# digidisk.net
KiCad netlist of a schematic drawn in Altium Designer
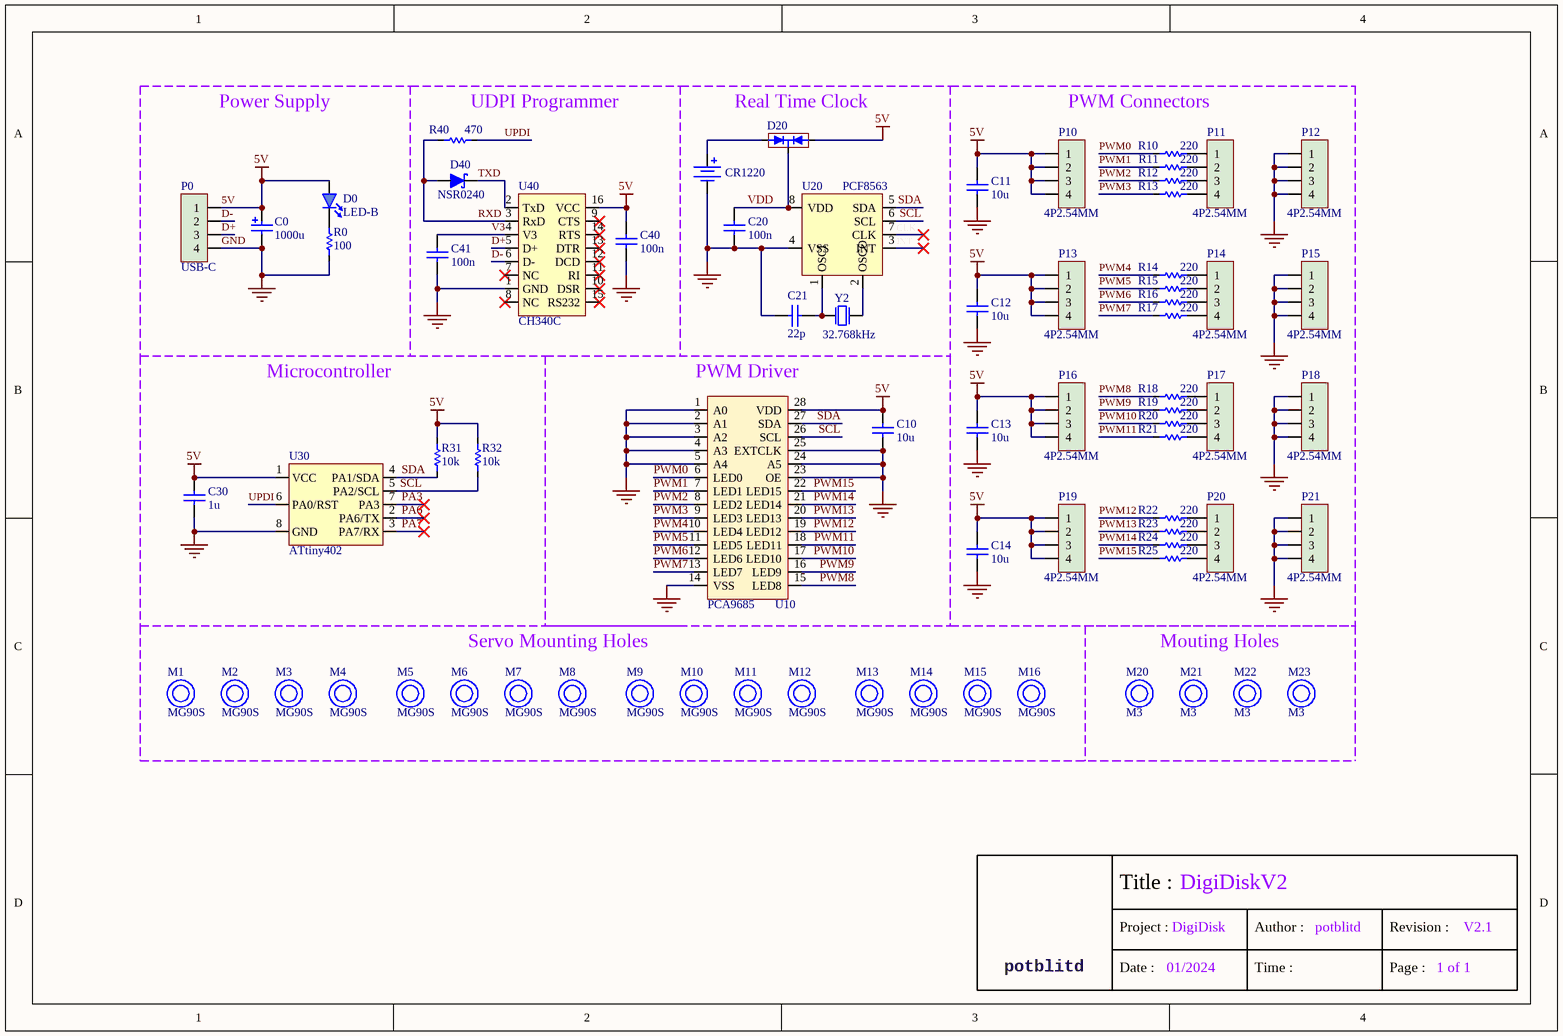
[diagram p0: digidisk.SchDoc]

(export (version "E")
  (design (tool "Eeschema 10.0.6"))
  (components
    (comp (ref "BT20")
      (value "CR1220")
      (footprint "CR1220-H")
      (description "Coin cell battery 3V")
      (libsource (lib "AltiumLib") (part "Battery 3V"))
    )
    (comp (ref "C0")
      (value "1000u")
      (footprint "10X10.2")
      (description "Electrolytic Capacitor")
      (libsource (lib "AltiumLib") (part "PCapacitor"))
    )
    (comp (ref "C10")
      (value "10u")
      (footprint "0603CM")
      (description "Capacitor 10u")
      (fields (field (name "Comment") "Capacitor"))
      (libsource (lib "Simulation Generic Components") (part "Capacitor"))
    )
    (comp (ref "C11")
      (value "10u")
      (footprint "0603CM")
      (description "Capacitor 10u")
      (fields (field (name "Comment") "Capacitor"))
      (libsource (lib "Simulation Generic Components") (part "Capacitor"))
    )
    (comp (ref "C12")
      (value "10u")
      (footprint "0603CM")
      (description "Capacitor 10u")
      (fields (field (name "Comment") "Capacitor"))
      (libsource (lib "Simulation Generic Components") (part "Capacitor"))
    )
    (comp (ref "C13")
      (value "10u")
      (footprint "0603CM")
      (description "Capacitor 10u")
      (fields (field (name "Comment") "Capacitor"))
      (libsource (lib "Simulation Generic Components") (part "Capacitor"))
    )
    (comp (ref "C14")
      (value "10u")
      (footprint "0603CM")
      (description "Capacitor 10u")
      (fields (field (name "Comment") "Capacitor"))
      (libsource (lib "Simulation Generic Components") (part "Capacitor"))
    )
    (comp (ref "C20")
      (value "100n")
      (footprint "0603CM")
      (description "Capacitor 100nF ±10% 50V")
      (fields (field (name "Comment") "Capacitor"))
      (libsource (lib "Simulation Generic Components") (part "Capacitor"))
    )
    (comp (ref "C21")
      (value "22p")
      (footprint "0603CM")
      (description "Capacitor 22pF ±5% 50V")
      (fields (field (name "Comment") "Capacitor"))
      (libsource (lib "Simulation Generic Components") (part "Capacitor"))
    )
    (comp (ref "C30")
      (value "Capacitor")
      (footprint "0603CM")
      (description "Capacitor 1uF")
      (fields (field (name "ALTIUM_VALUE") "1u"))
      (libsource (lib "Simulation Generic Components") (part "Capacitor"))
    )
    (comp (ref "C40")
      (value "100n")
      (footprint "0603CM")
      (description "Capacitor 100nF ±10% 50V")
      (fields (field (name "Comment") "Capacitor"))
      (libsource (lib "Simulation Generic Components") (part "Capacitor"))
    )
    (comp (ref "C41")
      (value "100n")
      (footprint "0603CM")
      (description "Capacitor 100nF ±10% 50V")
      (fields (field (name "Comment") "Capacitor"))
      (libsource (lib "Simulation Generic Components") (part "Capacitor"))
    )
    (comp (ref "D0")
      (value "LED-B")
      (footprint "0603DM")
      (description "General LED symbol")
      (libsource (lib "AltiumLib") (part "LED-B"))
    )
    (comp (ref "D20")
      (value "BAS40-05")
      (footprint "SOT23-3 M")
      (description "General symbol for a dual diode")
      (libsource (lib "AltiumLib") (part "Dual Diode 2"))
    )
    (comp (ref "D40")
      (value "NSR0240")
      (footprint "SOD-323 M")
      (description "Schottky Barrier Rectifiers")
      (libsource (lib "AltiumLib") (part "Schottky Diode"))
    )
    (comp (ref "M1")
      (value "MG90S")
      (footprint "HOLE-SG90-2")
      (description "Genreal symbol for mechanical mounting hole")
      (libsource (lib "AltiumLib") (part "Mounting Hole noGD"))
    )
    (comp (ref "M2")
      (value "MG90S")
      (footprint "HOLE-SG90-2")
      (description "Genreal symbol for mechanical mounting hole")
      (libsource (lib "AltiumLib") (part "Mounting Hole noGD"))
    )
    (comp (ref "M3")
      (value "MG90S")
      (footprint "HOLE-SG90-2")
      (description "Genreal symbol for mechanical mounting hole")
      (libsource (lib "AltiumLib") (part "Mounting Hole noGD"))
    )
    (comp (ref "M4")
      (value "MG90S")
      (footprint "HOLE-SG90-2")
      (description "Genreal symbol for mechanical mounting hole")
      (libsource (lib "AltiumLib") (part "Mounting Hole noGD"))
    )
    (comp (ref "M5")
      (value "MG90S")
      (footprint "HOLE-SG90-2")
      (description "Genreal symbol for mechanical mounting hole")
      (libsource (lib "AltiumLib") (part "Mounting Hole noGD"))
    )
    (comp (ref "M6")
      (value "MG90S")
      (footprint "HOLE-SG90-2")
      (description "Genreal symbol for mechanical mounting hole")
      (libsource (lib "AltiumLib") (part "Mounting Hole noGD"))
    )
    (comp (ref "M7")
      (value "MG90S")
      (footprint "HOLE-SG90-2")
      (description "Genreal symbol for mechanical mounting hole")
      (libsource (lib "AltiumLib") (part "Mounting Hole noGD"))
    )
    (comp (ref "M8")
      (value "MG90S")
      (footprint "HOLE-SG90-2")
      (description "Genreal symbol for mechanical mounting hole")
      (libsource (lib "AltiumLib") (part "Mounting Hole noGD"))
    )
    (comp (ref "M9")
      (value "MG90S")
      (footprint "HOLE-SG90-2")
      (description "Genreal symbol for mechanical mounting hole")
      (libsource (lib "AltiumLib") (part "Mounting Hole noGD"))
    )
    (comp (ref "M10")
      (value "MG90S")
      (footprint "HOLE-SG90-2")
      (description "Genreal symbol for mechanical mounting hole")
      (libsource (lib "AltiumLib") (part "Mounting Hole noGD"))
    )
    (comp (ref "M11")
      (value "MG90S")
      (footprint "HOLE-SG90-2")
      (description "Genreal symbol for mechanical mounting hole")
      (libsource (lib "AltiumLib") (part "Mounting Hole noGD"))
    )
    (comp (ref "M12")
      (value "MG90S")
      (footprint "HOLE-SG90-2")
      (description "Genreal symbol for mechanical mounting hole")
      (libsource (lib "AltiumLib") (part "Mounting Hole noGD"))
    )
    (comp (ref "M13")
      (value "MG90S")
      (footprint "HOLE-SG90-2")
      (description "Genreal symbol for mechanical mounting hole")
      (libsource (lib "AltiumLib") (part "Mounting Hole noGD"))
    )
    (comp (ref "M14")
      (value "MG90S")
      (footprint "HOLE-SG90-2")
      (description "Genreal symbol for mechanical mounting hole")
      (libsource (lib "AltiumLib") (part "Mounting Hole noGD"))
    )
    (comp (ref "M15")
      (value "MG90S")
      (footprint "HOLE-SG90-2")
      (description "Genreal symbol for mechanical mounting hole")
      (libsource (lib "AltiumLib") (part "Mounting Hole noGD"))
    )
    (comp (ref "M16")
      (value "MG90S")
      (footprint "HOLE-SG90-2")
      (description "Genreal symbol for mechanical mounting hole")
      (libsource (lib "AltiumLib") (part "Mounting Hole noGD"))
    )
    (comp (ref "M20")
      (value "M3")
      (footprint "HOLE-M3-simple")
      (description "Genreal symbol for mechanical mounting hole")
      (libsource (lib "AltiumLib") (part "Mounting Hole noGD"))
    )
    (comp (ref "M21")
      (value "M3")
      (footprint "HOLE-M3-simple")
      (description "Genreal symbol for mechanical mounting hole")
      (libsource (lib "AltiumLib") (part "Mounting Hole noGD"))
    )
    (comp (ref "M22")
      (value "M3")
      (footprint "HOLE-M3-simple")
      (description "Genreal symbol for mechanical mounting hole")
      (libsource (lib "AltiumLib") (part "Mounting Hole noGD"))
    )
    (comp (ref "M23")
      (value "M3")
      (footprint "HOLE-M3-simple")
      (description "Genreal symbol for mechanical mounting hole")
      (libsource (lib "AltiumLib") (part "Mounting Hole noGD"))
    )
    (comp (ref "P0")
      (value "USB-C")
      (footprint "USB-C module 2.8mm")
      (description "General 4-pin connection")
      (libsource (lib "") (part "4-pins Header_1"))
    )
    (comp (ref "P10")
      (value "4P2.54MM")
      (footprint "4P-2.54mm")
      (description "General 4-pin connection")
      (libsource (lib "AltiumLib") (part "4-pins Header"))
    )
    (comp (ref "P11")
      (value "4P2.54MM")
      (footprint "4P-2.54mm")
      (description "General 4-pin connection")
      (libsource (lib "AltiumLib") (part "4-pins Header"))
    )
    (comp (ref "P12")
      (value "4P2.54MM")
      (footprint "4P-2.54mm")
      (description "General 4-pin connection")
      (libsource (lib "AltiumLib") (part "4-pins Header"))
    )
    (comp (ref "P13")
      (value "4P2.54MM")
      (footprint "4P-2.54mm")
      (description "General 4-pin connection")
      (libsource (lib "AltiumLib") (part "4-pins Header"))
    )
    (comp (ref "P14")
      (value "4P2.54MM")
      (footprint "4P-2.54mm")
      (description "General 4-pin connection")
      (libsource (lib "AltiumLib") (part "4-pins Header"))
    )
    (comp (ref "P15")
      (value "4P2.54MM")
      (footprint "4P-2.54mm")
      (description "General 4-pin connection")
      (libsource (lib "AltiumLib") (part "4-pins Header"))
    )
    (comp (ref "P16")
      (value "4P2.54MM")
      (footprint "4P-2.54mm")
      (description "General 4-pin connection")
      (libsource (lib "AltiumLib") (part "4-pins Header"))
    )
    (comp (ref "P17")
      (value "4P2.54MM")
      (footprint "4P-2.54mm")
      (description "General 4-pin connection")
      (libsource (lib "AltiumLib") (part "4-pins Header"))
    )
    (comp (ref "P18")
      (value "4P2.54MM")
      (footprint "4P-2.54mm")
      (description "General 4-pin connection")
      (libsource (lib "AltiumLib") (part "4-pins Header"))
    )
    (comp (ref "P19")
      (value "4P2.54MM")
      (footprint "4P-2.54mm")
      (description "General 4-pin connection")
      (libsource (lib "AltiumLib") (part "4-pins Header"))
    )
    (comp (ref "P20")
      (value "4P2.54MM")
      (footprint "4P-2.54mm")
      (description "General 4-pin connection")
      (libsource (lib "AltiumLib") (part "4-pins Header"))
    )
    (comp (ref "P21")
      (value "4P2.54MM")
      (footprint "4P-2.54mm")
      (description "General 4-pin connection")
      (libsource (lib "AltiumLib") (part "4-pins Header"))
    )
    (comp (ref "R0")
      (value "100")
      (footprint "0603RM")
      (description "Resistor")
      (libsource (lib "AltiumLib") (part "RES"))
    )
    (comp (ref "R10")
      (value "220")
      (footprint "0603RM")
      (description "Resistor")
      (libsource (lib "AltiumLib") (part "RES"))
    )
    (comp (ref "R11")
      (value "220")
      (footprint "0603RM")
      (description "Resistor")
      (libsource (lib "AltiumLib") (part "RES"))
    )
    (comp (ref "R12")
      (value "220")
      (footprint "0603RM")
      (description "Resistor")
      (libsource (lib "AltiumLib") (part "RES"))
    )
    (comp (ref "R13")
      (value "220")
      (footprint "0603RM")
      (description "Resistor")
      (libsource (lib "AltiumLib") (part "RES"))
    )
    (comp (ref "R14")
      (value "220")
      (footprint "0603RM")
      (description "Resistor")
      (libsource (lib "AltiumLib") (part "RES"))
    )
    (comp (ref "R15")
      (value "220")
      (footprint "0603RM")
      (description "Resistor")
      (libsource (lib "AltiumLib") (part "RES"))
    )
    (comp (ref "R16")
      (value "220")
      (footprint "0603RM")
      (description "Resistor")
      (libsource (lib "AltiumLib") (part "RES"))
    )
    (comp (ref "R17")
      (value "220")
      (footprint "0603RM")
      (description "Resistor")
      (libsource (lib "AltiumLib") (part "RES"))
    )
    (comp (ref "R18")
      (value "220")
      (footprint "0603RM")
      (description "Resistor")
      (libsource (lib "AltiumLib") (part "RES"))
    )
    (comp (ref "R19")
      (value "220")
      (footprint "0603RM")
      (description "Resistor")
      (libsource (lib "AltiumLib") (part "RES"))
    )
    (comp (ref "R20")
      (value "220")
      (footprint "0603RM")
      (description "Resistor")
      (libsource (lib "AltiumLib") (part "RES"))
    )
    (comp (ref "R21")
      (value "220")
      (footprint "0603RM")
      (description "Resistor")
      (libsource (lib "AltiumLib") (part "RES"))
    )
    (comp (ref "R22")
      (value "220")
      (footprint "0603RM")
      (description "Resistor")
      (libsource (lib "AltiumLib") (part "RES"))
    )
    (comp (ref "R23")
      (value "220")
      (footprint "0603RM")
      (description "Resistor")
      (libsource (lib "AltiumLib") (part "RES"))
    )
    (comp (ref "R24")
      (value "220")
      (footprint "0603RM")
      (description "Resistor")
      (libsource (lib "AltiumLib") (part "RES"))
    )
    (comp (ref "R25")
      (value "220")
      (footprint "0603RM")
      (description "Resistor")
      (libsource (lib "AltiumLib") (part "RES"))
    )
    (comp (ref "R31")
      (value "10k")
      (footprint "0603RM")
      (description "Resistor")
      (libsource (lib "AltiumLib") (part "RES"))
    )
    (comp (ref "R32")
      (value "10k")
      (footprint "0603RM")
      (description "Resistor")
      (libsource (lib "AltiumLib") (part "RES"))
    )
    (comp (ref "R40")
      (value "470")
      (footprint "0603RM")
      (description "Resistor")
      (libsource (lib "AltiumLib") (part "RES"))
    )
    (comp (ref "U10")
      (value "PCA9685")
      (footprint "TSSOP-28 M")
      (description "16-channel, 12-bit PWM Fm+ I2C-bus LED controller")
      (libsource (lib "AltiumLib") (part "PCA9685"))
    )
    (comp (ref "U20")
      (value "PCF8563")
      (footprint "SOP-8 M")
      (description "IC real-time clock with alarm interrupt")
      (libsource (lib "AltiumLib") (part "RTC-8563"))
    )
    (comp (ref "U30")
      (value "ATtiny402")
      (footprint "SOP-8 M")
      (description "tiny AVR 8-pin microcontroller")
      (fields (field (name "COMPONENT") "ATtiny402"))
      (libsource (lib "AltiumLib") (part "ATtiny202/402"))
    )
    (comp (ref "U40")
      (value "CH340C")
      (footprint "SOP-16 M")
      (description "USB to serial")
      (libsource (lib "AltiumLib") (part "CH340C-A"))
    )
    (comp (ref "Y2")
      (value "32.768kHz")
      (footprint "FC135 M")
      (description "Crystal oscillator 32.768kHz 20ppm 12.5pF")
      (fields (field (name "Comment") "Oscillator"))
      (libsource (lib "AltiumLib") (part "XO-2"))
    )
  )
  (nets
    (net (code "1") (name "/CLK") (class "Default")
      (node (ref "U20") (pin "7") (pinfunction "CLK_7") (pintype "passive+no_connect"))
    )
    (net (code "2") (name "/D+") (class "Default")
      (node (ref "P0") (pin "3") (pinfunction "3_3") (pintype "passive"))
      (node (ref "U40") (pin "5") (pinfunction "D+_5") (pintype "passive"))
    )
    (net (code "3") (name "/D-") (class "Default")
      (node (ref "P0") (pin "2") (pinfunction "2_2") (pintype "passive"))
      (node (ref "U40") (pin "6") (pinfunction "D-_6") (pintype "passive"))
    )
    (net (code "4") (name "/INT") (class "Default")
      (node (ref "U20") (pin "3") (pinfunction "INT_3") (pintype "passive+no_connect"))
    )
    (net (code "5") (name "/PA3") (class "Default")
      (node (ref "U30") (pin "7") (pinfunction "PA3_7") (pintype "passive+no_connect"))
    )
    (net (code "6") (name "/PA6") (class "Default")
      (node (ref "U30") (pin "2") (pinfunction "PA6/TX_2") (pintype "passive+no_connect"))
    )
    (net (code "7") (name "/PA7") (class "Default")
      (node (ref "U30") (pin "3") (pinfunction "PA7/RX_3") (pintype "passive+no_connect"))
    )
    (net (code "8") (name "/PWM0") (class "Default")
      (node (ref "R10") (pin "2") (pinfunction "2_2") (pintype "passive"))
      (node (ref "U10") (pin "6") (pinfunction "LED0_6") (pintype "passive"))
    )
    (net (code "9") (name "/PWM1") (class "Default")
      (node (ref "R11") (pin "2") (pinfunction "2_2") (pintype "passive"))
      (node (ref "U10") (pin "7") (pinfunction "LED1_7") (pintype "passive"))
    )
    (net (code "10") (name "/PWM2") (class "Default")
      (node (ref "R12") (pin "2") (pinfunction "2_2") (pintype "passive"))
      (node (ref "U10") (pin "8") (pinfunction "LED2_8") (pintype "passive"))
    )
    (net (code "11") (name "/PWM3") (class "Default")
      (node (ref "R13") (pin "2") (pinfunction "2_2") (pintype "passive"))
      (node (ref "U10") (pin "9") (pinfunction "LED3_9") (pintype "passive"))
    )
    (net (code "12") (name "/PWM4") (class "Default")
      (node (ref "R14") (pin "2") (pinfunction "2_2") (pintype "passive"))
      (node (ref "U10") (pin "10") (pinfunction "LED4_10") (pintype "passive"))
    )
    (net (code "13") (name "/PWM5") (class "Default")
      (node (ref "R15") (pin "2") (pinfunction "2_2") (pintype "passive"))
      (node (ref "U10") (pin "11") (pinfunction "LED5_11") (pintype "passive"))
    )
    (net (code "14") (name "/PWM6") (class "Default")
      (node (ref "R16") (pin "2") (pinfunction "2_2") (pintype "passive"))
      (node (ref "U10") (pin "12") (pinfunction "LED6_12") (pintype "passive"))
    )
    (net (code "15") (name "/PWM7") (class "Default")
      (node (ref "R17") (pin "2") (pinfunction "2_2") (pintype "passive"))
      (node (ref "U10") (pin "13") (pinfunction "LED7_13") (pintype "passive"))
    )
    (net (code "16") (name "/PWM8") (class "Default")
      (node (ref "R18") (pin "2") (pinfunction "2_2") (pintype "passive"))
      (node (ref "U10") (pin "15") (pinfunction "LED8_15") (pintype "passive"))
    )
    (net (code "17") (name "/PWM9") (class "Default")
      (node (ref "R19") (pin "2") (pinfunction "2_2") (pintype "passive"))
      (node (ref "U10") (pin "16") (pinfunction "LED9_16") (pintype "passive"))
    )
    (net (code "18") (name "/PWM10") (class "Default")
      (node (ref "R20") (pin "2") (pinfunction "2_2") (pintype "passive"))
      (node (ref "U10") (pin "17") (pinfunction "LED10_17") (pintype "passive"))
    )
    (net (code "19") (name "/PWM11") (class "Default")
      (node (ref "R21") (pin "2") (pinfunction "2_2") (pintype "passive"))
      (node (ref "U10") (pin "18") (pinfunction "LED11_18") (pintype "passive"))
    )
    (net (code "20") (name "/PWM12") (class "Default")
      (node (ref "R22") (pin "2") (pinfunction "2_2") (pintype "passive"))
      (node (ref "U10") (pin "19") (pinfunction "LED12_19") (pintype "passive"))
    )
    (net (code "21") (name "/PWM13") (class "Default")
      (node (ref "R23") (pin "2") (pinfunction "2_2") (pintype "passive"))
      (node (ref "U10") (pin "20") (pinfunction "LED13_20") (pintype "passive"))
    )
    (net (code "22") (name "/PWM14") (class "Default")
      (node (ref "R24") (pin "2") (pinfunction "2_2") (pintype "passive"))
      (node (ref "U10") (pin "21") (pinfunction "LED14_21") (pintype "passive"))
    )
    (net (code "23") (name "/PWM15") (class "Default")
      (node (ref "R25") (pin "2") (pinfunction "2_2") (pintype "passive"))
      (node (ref "U10") (pin "22") (pinfunction "LED15_22") (pintype "passive"))
    )
    (net (code "24") (name "/RXD") (class "Default")
      (node (ref "D40") (pin "1") (pinfunction "A_1") (pintype "passive"))
      (node (ref "R40") (pin "2") (pinfunction "2_2") (pintype "passive"))
      (node (ref "U40") (pin "3") (pinfunction "RxD_3") (pintype "passive"))
    )
    (net (code "25") (name "/SCL") (class "Default")
      (node (ref "R32") (pin "1") (pinfunction "1_1") (pintype "passive"))
      (node (ref "U10") (pin "26") (pinfunction "SCL_26") (pintype "passive"))
      (node (ref "U20") (pin "6") (pinfunction "SCL_6") (pintype "passive"))
      (node (ref "U30") (pin "5") (pinfunction "PA2/SCL_5") (pintype "passive"))
    )
    (net (code "26") (name "/SDA") (class "Default")
      (node (ref "R31") (pin "1") (pinfunction "1_1") (pintype "passive"))
      (node (ref "U10") (pin "27") (pinfunction "SDA_27") (pintype "passive"))
      (node (ref "U20") (pin "5") (pinfunction "SDA_5") (pintype "passive"))
      (node (ref "U30") (pin "4") (pinfunction "PA1/SDA_4") (pintype "passive"))
    )
    (net (code "27") (name "/TXD") (class "Default")
      (node (ref "D40") (pin "2") (pinfunction "C_2") (pintype "passive"))
      (node (ref "U40") (pin "2") (pinfunction "TxD_2") (pintype "passive"))
    )
    (net (code "28") (name "/UPDI") (class "Default")
      (node (ref "R40") (pin "1") (pinfunction "1_1") (pintype "passive"))
      (node (ref "U30") (pin "6") (pinfunction "PA0/RST_6") (pintype "passive"))
    )
    (net (code "29") (name "/V3") (class "Default")
      (node (ref "C41") (pin "1") (pinfunction "1_1") (pintype "passive"))
      (node (ref "U40") (pin "4") (pinfunction "V3_4") (pintype "passive"))
    )
    (net (code "30") (name "/VDD") (class "Default")
      (node (ref "C20") (pin "1") (pinfunction "1_1") (pintype "passive"))
      (node (ref "D20") (pin "3") (pinfunction "3_3") (pintype "passive"))
      (node (ref "U20") (pin "8") (pinfunction "VDD_8") (pintype "passive"))
    )
    (net (code "31") (name "5V") (class "Default")
      (node (ref "C0") (pin "1") (pinfunction "+_1") (pintype "passive"))
      (node (ref "C10") (pin "1") (pinfunction "1_1") (pintype "passive"))
      (node (ref "C11") (pin "1") (pinfunction "1_1") (pintype "passive"))
      (node (ref "C12") (pin "1") (pinfunction "1_1") (pintype "passive"))
      (node (ref "C13") (pin "1") (pinfunction "1_1") (pintype "passive"))
      (node (ref "C14") (pin "1") (pinfunction "1_1") (pintype "passive"))
      (node (ref "C30") (pin "2") (pinfunction "2_2") (pintype "passive"))
      (node (ref "C40") (pin "1") (pinfunction "1_1") (pintype "passive"))
      (node (ref "D0") (pin "1") (pintype "passive"))
      (node (ref "D20") (pin "1") (pinfunction "1_1") (pintype "passive"))
      (node (ref "P0") (pin "1") (pinfunction "1_1") (pintype "passive"))
      (node (ref "P10") (pin "1") (pinfunction "1_1") (pintype "passive"))
      (node (ref "P10") (pin "2") (pinfunction "2_2") (pintype "passive"))
      (node (ref "P10") (pin "3") (pinfunction "3_3") (pintype "passive"))
      (node (ref "P10") (pin "4") (pinfunction "4_4") (pintype "passive"))
      (node (ref "P13") (pin "1") (pinfunction "1_1") (pintype "passive"))
      (node (ref "P13") (pin "2") (pinfunction "2_2") (pintype "passive"))
      (node (ref "P13") (pin "3") (pinfunction "3_3") (pintype "passive"))
      (node (ref "P13") (pin "4") (pinfunction "4_4") (pintype "passive"))
      (node (ref "P16") (pin "1") (pinfunction "1_1") (pintype "passive"))
      (node (ref "P16") (pin "2") (pinfunction "2_2") (pintype "passive"))
      (node (ref "P16") (pin "3") (pinfunction "3_3") (pintype "passive"))
      (node (ref "P16") (pin "4") (pinfunction "4_4") (pintype "passive"))
      (node (ref "P19") (pin "1") (pinfunction "1_1") (pintype "passive"))
      (node (ref "P19") (pin "2") (pinfunction "2_2") (pintype "passive"))
      (node (ref "P19") (pin "3") (pinfunction "3_3") (pintype "passive"))
      (node (ref "P19") (pin "4") (pinfunction "4_4") (pintype "passive"))
      (node (ref "R31") (pin "2") (pinfunction "2_2") (pintype "passive"))
      (node (ref "R32") (pin "2") (pinfunction "2_2") (pintype "passive"))
      (node (ref "U10") (pin "28") (pinfunction "VDD_28") (pintype "passive"))
      (node (ref "U30") (pin "1") (pinfunction "VCC_1") (pintype "passive"))
      (node (ref "U40") (pin "16") (pinfunction "VCC_16") (pintype "passive"))
    )
    (net (code "32") (name "GND") (class "Default")
      (node (ref "BT20") (pin "2") (pinfunction "-_2") (pintype "passive"))
      (node (ref "C0") (pin "2") (pinfunction "-_2") (pintype "passive"))
      (node (ref "C10") (pin "2") (pinfunction "2_2") (pintype "passive"))
      (node (ref "C11") (pin "2") (pinfunction "2_2") (pintype "passive"))
      (node (ref "C12") (pin "2") (pinfunction "2_2") (pintype "passive"))
      (node (ref "C13") (pin "2") (pinfunction "2_2") (pintype "passive"))
      (node (ref "C14") (pin "2") (pinfunction "2_2") (pintype "passive"))
      (node (ref "C20") (pin "2") (pinfunction "2_2") (pintype "passive"))
      (node (ref "C21") (pin "2") (pinfunction "2_2") (pintype "passive"))
      (node (ref "C30") (pin "1") (pinfunction "1_1") (pintype "passive"))
      (node (ref "C40") (pin "2") (pinfunction "2_2") (pintype "passive"))
      (node (ref "C41") (pin "2") (pinfunction "2_2") (pintype "passive"))
      (node (ref "P0") (pin "4") (pinfunction "4_4") (pintype "passive"))
      (node (ref "P12") (pin "1") (pinfunction "1_1") (pintype "passive"))
      (node (ref "P12") (pin "2") (pinfunction "2_2") (pintype "passive"))
      (node (ref "P12") (pin "3") (pinfunction "3_3") (pintype "passive"))
      (node (ref "P12") (pin "4") (pinfunction "4_4") (pintype "passive"))
      (node (ref "P15") (pin "1") (pinfunction "1_1") (pintype "passive"))
      (node (ref "P15") (pin "2") (pinfunction "2_2") (pintype "passive"))
      (node (ref "P15") (pin "3") (pinfunction "3_3") (pintype "passive"))
      (node (ref "P15") (pin "4") (pinfunction "4_4") (pintype "passive"))
      (node (ref "P18") (pin "1") (pinfunction "1_1") (pintype "passive"))
      (node (ref "P18") (pin "2") (pinfunction "2_2") (pintype "passive"))
      (node (ref "P18") (pin "3") (pinfunction "3_3") (pintype "passive"))
      (node (ref "P18") (pin "4") (pinfunction "4_4") (pintype "passive"))
      (node (ref "P21") (pin "1") (pinfunction "1_1") (pintype "passive"))
      (node (ref "P21") (pin "2") (pinfunction "2_2") (pintype "passive"))
      (node (ref "P21") (pin "3") (pinfunction "3_3") (pintype "passive"))
      (node (ref "P21") (pin "4") (pinfunction "4_4") (pintype "passive"))
      (node (ref "R0") (pin "1") (pinfunction "1_1") (pintype "passive"))
      (node (ref "U10") (pin "1") (pinfunction "A0_1") (pintype "passive"))
      (node (ref "U10") (pin "14") (pinfunction "VSS_14") (pintype "passive"))
      (node (ref "U10") (pin "2") (pinfunction "A1_2") (pintype "passive"))
      (node (ref "U10") (pin "23") (pinfunction "OE_23") (pintype "passive"))
      (node (ref "U10") (pin "24") (pinfunction "A5_24") (pintype "passive"))
      (node (ref "U10") (pin "25") (pinfunction "EXTCLK_25") (pintype "passive"))
      (node (ref "U10") (pin "3") (pinfunction "A2_3") (pintype "passive"))
      (node (ref "U10") (pin "4") (pinfunction "A3_4") (pintype "passive"))
      (node (ref "U10") (pin "5") (pinfunction "A4_5") (pintype "passive"))
      (node (ref "U20") (pin "4") (pinfunction "VSS_4") (pintype "passive"))
      (node (ref "U30") (pin "8") (pinfunction "GND_8") (pintype "passive"))
      (node (ref "U40") (pin "1") (pinfunction "GND_1") (pintype "passive"))
    )
    (net (code "33") (name "Net-(BT20-+)") (class "Default")
      (node (ref "BT20") (pin "1") (pinfunction "+_1") (pintype "passive"))
      (node (ref "D20") (pin "2") (pinfunction "2_2") (pintype "passive"))
    )
    (net (code "34") (name "Net-(D0-Pad2)") (class "Default")
      (node (ref "D0") (pin "2") (pintype "passive"))
      (node (ref "R0") (pin "2") (pinfunction "2_2") (pintype "passive"))
    )
    (net (code "35") (name "Net-(P11-Pad1)") (class "Default")
      (node (ref "P11") (pin "1") (pinfunction "1_1") (pintype "passive"))
      (node (ref "R10") (pin "1") (pinfunction "1_1") (pintype "passive"))
    )
    (net (code "36") (name "Net-(P11-Pad2)") (class "Default")
      (node (ref "P11") (pin "2") (pinfunction "2_2") (pintype "passive"))
      (node (ref "R11") (pin "1") (pinfunction "1_1") (pintype "passive"))
    )
    (net (code "37") (name "Net-(P11-Pad3)") (class "Default")
      (node (ref "P11") (pin "3") (pinfunction "3_3") (pintype "passive"))
      (node (ref "R12") (pin "1") (pinfunction "1_1") (pintype "passive"))
    )
    (net (code "38") (name "Net-(P11-Pad4)") (class "Default")
      (node (ref "P11") (pin "4") (pinfunction "4_4") (pintype "passive"))
      (node (ref "R13") (pin "1") (pinfunction "1_1") (pintype "passive"))
    )
    (net (code "39") (name "Net-(P14-Pad1)") (class "Default")
      (node (ref "P14") (pin "1") (pinfunction "1_1") (pintype "passive"))
      (node (ref "R14") (pin "1") (pinfunction "1_1") (pintype "passive"))
    )
    (net (code "40") (name "Net-(P14-Pad2)") (class "Default")
      (node (ref "P14") (pin "2") (pinfunction "2_2") (pintype "passive"))
      (node (ref "R15") (pin "1") (pinfunction "1_1") (pintype "passive"))
    )
    (net (code "41") (name "Net-(P14-Pad3)") (class "Default")
      (node (ref "P14") (pin "3") (pinfunction "3_3") (pintype "passive"))
      (node (ref "R16") (pin "1") (pinfunction "1_1") (pintype "passive"))
    )
    (net (code "42") (name "Net-(P14-Pad4)") (class "Default")
      (node (ref "P14") (pin "4") (pinfunction "4_4") (pintype "passive"))
      (node (ref "R17") (pin "1") (pinfunction "1_1") (pintype "passive"))
    )
    (net (code "43") (name "Net-(P17-Pad1)") (class "Default")
      (node (ref "P17") (pin "1") (pinfunction "1_1") (pintype "passive"))
      (node (ref "R18") (pin "1") (pinfunction "1_1") (pintype "passive"))
    )
    (net (code "44") (name "Net-(P17-Pad2)") (class "Default")
      (node (ref "P17") (pin "2") (pinfunction "2_2") (pintype "passive"))
      (node (ref "R19") (pin "1") (pinfunction "1_1") (pintype "passive"))
    )
    (net (code "45") (name "Net-(P17-Pad3)") (class "Default")
      (node (ref "P17") (pin "3") (pinfunction "3_3") (pintype "passive"))
      (node (ref "R20") (pin "1") (pinfunction "1_1") (pintype "passive"))
    )
    (net (code "46") (name "Net-(P17-Pad4)") (class "Default")
      (node (ref "P17") (pin "4") (pinfunction "4_4") (pintype "passive"))
      (node (ref "R21") (pin "1") (pinfunction "1_1") (pintype "passive"))
    )
    (net (code "47") (name "Net-(P20-Pad1)") (class "Default")
      (node (ref "P20") (pin "1") (pinfunction "1_1") (pintype "passive"))
      (node (ref "R22") (pin "1") (pinfunction "1_1") (pintype "passive"))
    )
    (net (code "48") (name "Net-(P20-Pad2)") (class "Default")
      (node (ref "P20") (pin "2") (pinfunction "2_2") (pintype "passive"))
      (node (ref "R23") (pin "1") (pinfunction "1_1") (pintype "passive"))
    )
    (net (code "49") (name "Net-(P20-Pad3)") (class "Default")
      (node (ref "P20") (pin "3") (pinfunction "3_3") (pintype "passive"))
      (node (ref "R24") (pin "1") (pinfunction "1_1") (pintype "passive"))
    )
    (net (code "50") (name "Net-(P20-Pad4)") (class "Default")
      (node (ref "P20") (pin "4") (pinfunction "4_4") (pintype "passive"))
      (node (ref "R25") (pin "1") (pinfunction "1_1") (pintype "passive"))
    )
    (net (code "51") (name "Net-(U20-OSCI)") (class "Default")
      (node (ref "C21") (pin "1") (pinfunction "1_1") (pintype "passive"))
      (node (ref "U20") (pin "1") (pinfunction "OSCI_1") (pintype "passive"))
      (node (ref "Y2") (pin "2") (pinfunction "2_2") (pintype "passive"))
    )
    (net (code "52") (name "Net-(U20-OSCO)") (class "Default")
      (node (ref "U20") (pin "2") (pinfunction "OSCO_2") (pintype "passive"))
      (node (ref "Y2") (pin "1") (pinfunction "1_1") (pintype "passive"))
    )
    (net (code "53") (name "unconnected-(U40-CTS-Pad9)") (class "Default")
      (node (ref "U40") (pin "9") (pinfunction "CTS_9") (pintype "passive+no_connect"))
    )
    (net (code "54") (name "unconnected-(U40-DCD-Pad12)") (class "Default")
      (node (ref "U40") (pin "12") (pinfunction "DCD_12") (pintype "passive+no_connect"))
    )
    (net (code "55") (name "unconnected-(U40-DSR-Pad10)") (class "Default")
      (node (ref "U40") (pin "10") (pinfunction "DSR_10") (pintype "passive+no_connect"))
    )
    (net (code "56") (name "unconnected-(U40-DTR-Pad13)") (class "Default")
      (node (ref "U40") (pin "13") (pinfunction "DTR_13") (pintype "passive+no_connect"))
    )
    (net (code "57") (name "unconnected-(U40-NC-Pad7)") (class "Default")
      (node (ref "U40") (pin "7") (pinfunction "NC_7") (pintype "passive+no_connect"))
    )
    (net (code "58") (name "unconnected-(U40-NC-Pad8)") (class "Default")
      (node (ref "U40") (pin "8") (pinfunction "NC_8") (pintype "passive+no_connect"))
    )
    (net (code "59") (name "unconnected-(U40-RI-Pad11)") (class "Default")
      (node (ref "U40") (pin "11") (pinfunction "RI_11") (pintype "passive+no_connect"))
    )
    (net (code "60") (name "unconnected-(U40-RS232-Pad15)") (class "Default")
      (node (ref "U40") (pin "15") (pinfunction "RS232_15") (pintype "passive+no_connect"))
    )
    (net (code "61") (name "unconnected-(U40-RTS-Pad14)") (class "Default")
      (node (ref "U40") (pin "14") (pinfunction "RTS_14") (pintype "passive+no_connect"))
    )
  )
)
